# 4.net
KiCad netlist of a schematic drawn in Altium Designer
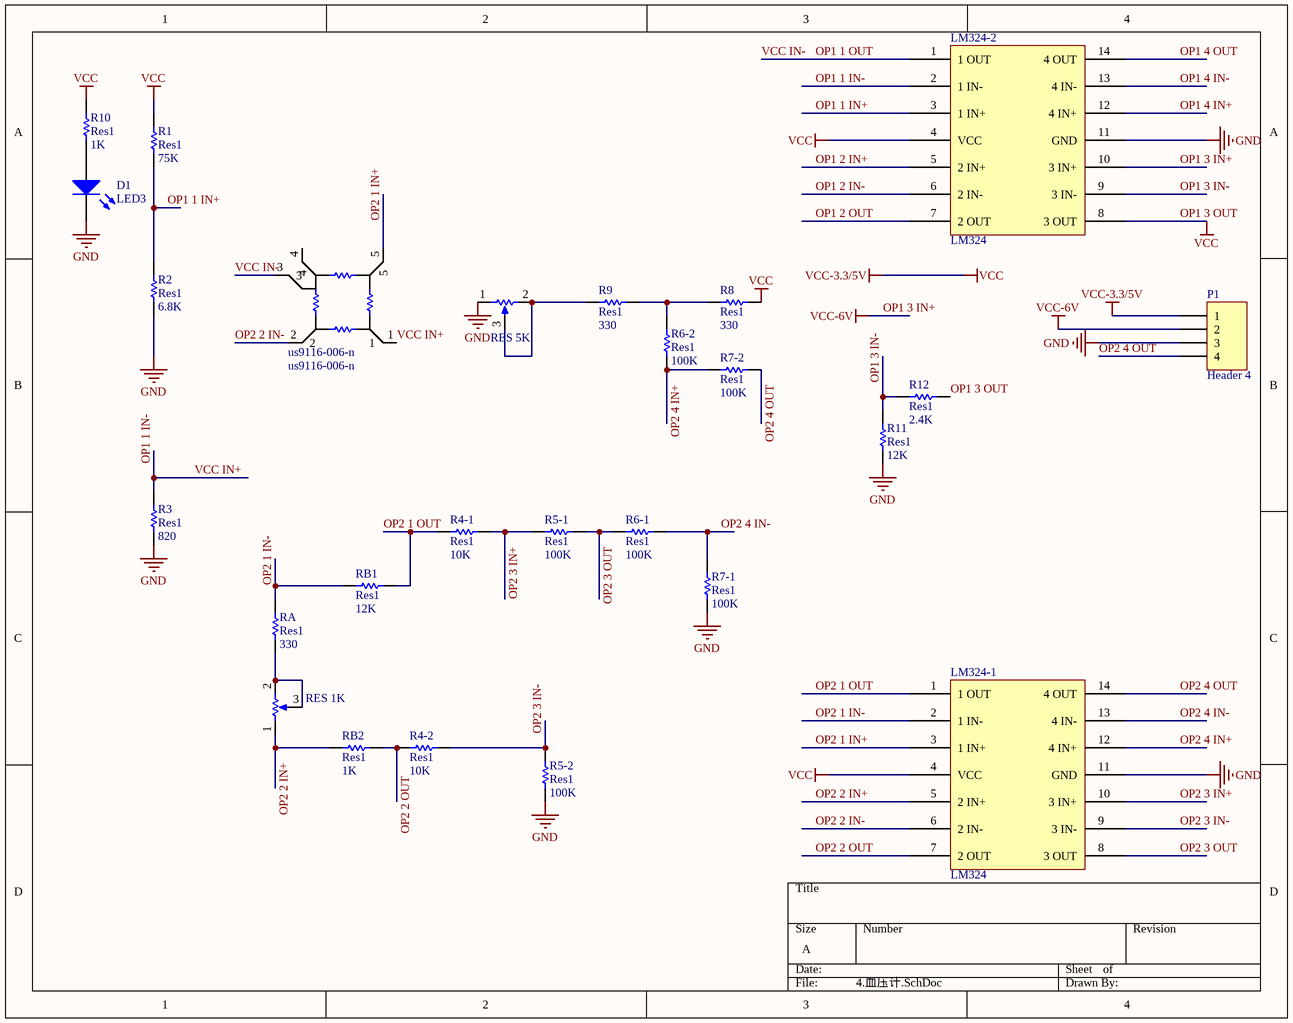
[diagram p0: 4.血压计.SchDoc]

(export (version "E")
  (design (tool "Eeschema 10.0.6"))
  (components
    (comp (ref "D1")
      (value "LED3")
      (footprint "LED/CAP/RES 0603")
      (description "Typical BLUE SiC LED")
      (fields (field (name "PUBLISHER") "Altium Limited"))
      (libsource (lib "Miscellaneous Devices") (part "LED3"))
    )
    (comp (ref "LM324-1")
      (value "LM324")
      (footprint "LM324")
      (libsource (lib "my Integrated lib ") (part "LM324"))
    )
    (comp (ref "LM324-2")
      (value "LM324")
      (footprint "LM324")
      (libsource (lib "my Integrated lib ") (part "LM324"))
    )
    (comp (ref "P1")
      (value "Header 4")
      (footprint "HDR1X4")
      (description "Header, 4-Pin")
      (fields (field (name "PUBLISHER") "Altium Limited"))
      (libsource (lib "Miscellaneous Connectors") (part "Header 4"))
    )
    (comp (ref "R1")
      (value "Res1")
      (footprint "LED/CAP/RES 0603")
      (description "Resistor")
      (fields (field (name "ALTIUM_VALUE") "75K") (field (name "PUBLISHER") "Altium Limited"))
      (libsource (lib "Miscellaneous Devices") (part "Res1"))
    )
    (comp (ref "R2")
      (value "Res1")
      (footprint "LED/CAP/RES 0603")
      (description "Resistor")
      (fields (field (name "ALTIUM_VALUE") "6.8K") (field (name "PUBLISHER") "Altium Limited"))
      (libsource (lib "Miscellaneous Devices") (part "Res1"))
    )
    (comp (ref "R3")
      (value "Res1")
      (footprint "LED/CAP/RES 0603")
      (description "Resistor")
      (fields (field (name "ALTIUM_VALUE") "820") (field (name "PUBLISHER") "Altium Limited"))
      (libsource (lib "Miscellaneous Devices") (part "Res1"))
    )
    (comp (ref "R4-1")
      (value "Res1")
      (footprint "LED/CAP/RES 0603")
      (description "Resistor")
      (fields (field (name "ALTIUM_VALUE") "10K") (field (name "PUBLISHER") "Altium Limited"))
      (libsource (lib "Miscellaneous Devices") (part "Res1"))
    )
    (comp (ref "R4-2")
      (value "Res1")
      (footprint "LED/CAP/RES 0603")
      (description "Resistor")
      (fields (field (name "ALTIUM_VALUE") "10K") (field (name "PUBLISHER") "Altium Limited"))
      (libsource (lib "Miscellaneous Devices") (part "Res1"))
    )
    (comp (ref "R5-1")
      (value "Res1")
      (footprint "LED/CAP/RES 0603")
      (description "Resistor")
      (fields (field (name "ALTIUM_VALUE") "100K") (field (name "PUBLISHER") "Altium Limited"))
      (libsource (lib "Miscellaneous Devices") (part "Res1"))
    )
    (comp (ref "R5-2")
      (value "Res1")
      (footprint "LED/CAP/RES 0603")
      (description "Resistor")
      (fields (field (name "ALTIUM_VALUE") "100K") (field (name "PUBLISHER") "Altium Limited"))
      (libsource (lib "Miscellaneous Devices") (part "Res1"))
    )
    (comp (ref "R6-1")
      (value "Res1")
      (footprint "LED/CAP/RES 0603")
      (description "Resistor")
      (fields (field (name "ALTIUM_VALUE") "100K") (field (name "PUBLISHER") "Altium Limited"))
      (libsource (lib "Miscellaneous Devices") (part "Res1"))
    )
    (comp (ref "R6-2")
      (value "Res1")
      (footprint "LED/CAP/RES 0603")
      (description "Resistor")
      (fields (field (name "ALTIUM_VALUE") "100K") (field (name "PUBLISHER") "Altium Limited"))
      (libsource (lib "Miscellaneous Devices") (part "Res1"))
    )
    (comp (ref "R7-1")
      (value "Res1")
      (footprint "LED/CAP/RES 0603")
      (description "Resistor")
      (fields (field (name "ALTIUM_VALUE") "100K") (field (name "PUBLISHER") "Altium Limited"))
      (libsource (lib "Miscellaneous Devices") (part "Res1"))
    )
    (comp (ref "R7-2")
      (value "Res1")
      (footprint "LED/CAP/RES 0603")
      (description "Resistor")
      (fields (field (name "ALTIUM_VALUE") "100K") (field (name "PUBLISHER") "Altium Limited"))
      (libsource (lib "Miscellaneous Devices") (part "Res1"))
    )
    (comp (ref "R8")
      (value "Res1")
      (footprint "LED/CAP/RES 0603")
      (description "Resistor")
      (fields (field (name "ALTIUM_VALUE") "330") (field (name "PUBLISHER") "Altium Limited"))
      (libsource (lib "Miscellaneous Devices") (part "Res1"))
    )
    (comp (ref "R9")
      (value "Res1")
      (footprint "LED/CAP/RES 0603")
      (description "Resistor")
      (fields (field (name "ALTIUM_VALUE") "330") (field (name "PUBLISHER") "Altium Limited"))
      (libsource (lib "Miscellaneous Devices") (part "Res1"))
    )
    (comp (ref "R10")
      (value "Res1")
      (footprint "LED/CAP/RES 0603")
      (description "Resistor")
      (fields (field (name "ALTIUM_VALUE") "1K") (field (name "PUBLISHER") "Altium Limited"))
      (libsource (lib "Miscellaneous Devices") (part "Res1"))
    )
    (comp (ref "R11")
      (value "Res1")
      (footprint "LED/CAP/RES 0603")
      (description "Resistor")
      (fields (field (name "ALTIUM_VALUE") "12K") (field (name "PUBLISHER") "Altium Limited"))
      (libsource (lib "Miscellaneous Devices") (part "Res1"))
    )
    (comp (ref "R12")
      (value "Res1")
      (footprint "LED/CAP/RES 0603")
      (description "Resistor")
      (fields (field (name "ALTIUM_VALUE") "2.4K") (field (name "PUBLISHER") "Altium Limited"))
      (libsource (lib "Miscellaneous Devices") (part "Res1"))
    )
    (comp (ref "RA")
      (value "Res1")
      (footprint "LED/CAP/RES 0603")
      (description "Resistor")
      (fields (field (name "ALTIUM_VALUE") "330") (field (name "PUBLISHER") "Altium Limited"))
      (libsource (lib "Miscellaneous Devices") (part "Res1"))
    )
    (comp (ref "RB1")
      (value "Res1")
      (footprint "LED/CAP/RES 0603")
      (description "Resistor")
      (fields (field (name "ALTIUM_VALUE") "12K") (field (name "PUBLISHER") "Altium Limited"))
      (libsource (lib "Miscellaneous Devices") (part "Res1"))
    )
    (comp (ref "RB2")
      (value "Res1")
      (footprint "LED/CAP/RES 0603")
      (description "Resistor")
      (fields (field (name "ALTIUM_VALUE") "1K") (field (name "PUBLISHER") "Altium Limited"))
      (libsource (lib "Miscellaneous Devices") (part "Res1"))
    )
    (comp (ref "RES 1K")
      (value "RES POT")
      (footprint "RES POT")
      (libsource (lib "my Integrated lib ") (part "RES POT"))
    )
    (comp (ref "RES 5K")
      (value "RES POT")
      (footprint "RES POT")
      (libsource (lib "my Integrated lib ") (part "RES POT"))
    )
    (comp (ref "us9116-006-n")
      (value "us9116-006-n")
      (footprint "us9116-006-n")
      (libsource (lib "my Integrated lib ") (part "us9116-006-n"))
    )
  )
  (nets
    (net (code "1") (name "/OP1 1 IN+") (class "Default")
      (node (ref "LM324-2") (pin "3") (pinfunction "1_IN+_3") (pintype "passive"))
      (node (ref "R1") (pin "1") (pinfunction "1_1") (pintype "passive"))
      (node (ref "R2") (pin "2") (pinfunction "2_2") (pintype "passive"))
    )
    (net (code "2") (name "/OP1 1 IN-") (class "Default")
      (node (ref "LM324-2") (pin "2") (pinfunction "1_IN-_2") (pintype "passive"))
      (node (ref "R3") (pin "1") (pinfunction "1_1") (pintype "passive"))
      (node (ref "us9116-006-n") (pin "1") (pinfunction "1_1") (pintype "passive"))
    )
    (net (code "3") (name "/OP1 1 OUT") (class "Default")
      (node (ref "LM324-2") (pin "1") (pinfunction "1_OUT_1") (pintype "passive"))
      (node (ref "us9116-006-n") (pin "3") (pinfunction "3_3") (pintype "passive"))
    )
    (net (code "4") (name "/OP1 2 IN+") (class "Default")
      (node (ref "LM324-2") (pin "5") (pinfunction "2_IN+_5") (pintype "passive"))
    )
    (net (code "5") (name "/OP1 2 IN-") (class "Default")
      (node (ref "LM324-2") (pin "6") (pinfunction "2_IN-_6") (pintype "passive"))
    )
    (net (code "6") (name "/OP1 2 OUT") (class "Default")
      (node (ref "LM324-2") (pin "7") (pinfunction "2_OUT_7") (pintype "passive"))
    )
    (net (code "7") (name "/OP1 3 IN-") (class "Default")
      (node (ref "LM324-2") (pin "9") (pinfunction "3_IN-_9") (pintype "passive"))
      (node (ref "R11") (pin "1") (pinfunction "1_1") (pintype "passive"))
      (node (ref "R12") (pin "2") (pinfunction "2_2") (pintype "passive"))
    )
    (net (code "8") (name "/OP1 4 IN+") (class "Default")
      (node (ref "LM324-2") (pin "12") (pinfunction "4_IN+_12") (pintype "passive"))
    )
    (net (code "9") (name "/OP1 4 IN-") (class "Default")
      (node (ref "LM324-2") (pin "13") (pinfunction "4_IN-_13") (pintype "passive"))
    )
    (net (code "10") (name "/OP1 4 OUT") (class "Default")
      (node (ref "LM324-2") (pin "14") (pinfunction "4_OUT_14") (pintype "passive"))
    )
    (net (code "11") (name "/OP2 1 IN+") (class "Default")
      (node (ref "LM324-1") (pin "3") (pinfunction "1_IN+_3") (pintype "passive"))
      (node (ref "us9116-006-n") (pin "5") (pinfunction "5_5") (pintype "passive"))
    )
    (net (code "12") (name "/OP2 1 IN-") (class "Default")
      (node (ref "LM324-1") (pin "2") (pinfunction "1_IN-_2") (pintype "passive"))
      (node (ref "RA") (pin "2") (pinfunction "2_2") (pintype "passive"))
      (node (ref "RB1") (pin "2") (pinfunction "2_2") (pintype "passive"))
    )
    (net (code "13") (name "/OP2 1 OUT") (class "Default")
      (node (ref "LM324-1") (pin "1") (pinfunction "1_OUT_1") (pintype "passive"))
      (node (ref "R4-1") (pin "2") (pinfunction "2_2") (pintype "passive"))
      (node (ref "RB1") (pin "1") (pinfunction "1_1") (pintype "passive"))
    )
    (net (code "14") (name "/OP2 2 IN+") (class "Default")
      (node (ref "LM324-1") (pin "5") (pinfunction "2_IN+_5") (pintype "passive"))
      (node (ref "RB2") (pin "2") (pinfunction "2_2") (pintype "passive"))
      (node (ref "RES 1K") (pin "1") (pinfunction "TOP_1") (pintype "passive"))
    )
    (net (code "15") (name "/OP2 2 IN-") (class "Default")
      (node (ref "LM324-1") (pin "6") (pinfunction "2_IN-_6") (pintype "passive"))
      (node (ref "us9116-006-n") (pin "2") (pinfunction "2_2") (pintype "passive"))
    )
    (net (code "16") (name "/OP2 2 OUT") (class "Default")
      (node (ref "LM324-1") (pin "7") (pinfunction "2_OUT_7") (pintype "passive"))
      (node (ref "R4-2") (pin "2") (pinfunction "2_2") (pintype "passive"))
      (node (ref "RB2") (pin "1") (pinfunction "1_1") (pintype "passive"))
    )
    (net (code "17") (name "/OP2 3 IN+") (class "Default")
      (node (ref "LM324-1") (pin "10") (pinfunction "3_IN+_10") (pintype "passive"))
      (node (ref "R4-1") (pin "1") (pinfunction "1_1") (pintype "passive"))
      (node (ref "R5-1") (pin "2") (pinfunction "2_2") (pintype "passive"))
    )
    (net (code "18") (name "/OP2 3 IN-") (class "Default")
      (node (ref "LM324-1") (pin "9") (pinfunction "3_IN-_9") (pintype "passive"))
      (node (ref "R4-2") (pin "1") (pinfunction "1_1") (pintype "passive"))
      (node (ref "R5-2") (pin "1") (pinfunction "1_1") (pintype "passive"))
    )
    (net (code "19") (name "/OP2 3 OUT") (class "Default")
      (node (ref "LM324-1") (pin "8") (pinfunction "3_OUT_8") (pintype "passive"))
      (node (ref "R5-1") (pin "1") (pinfunction "1_1") (pintype "passive"))
      (node (ref "R6-1") (pin "2") (pinfunction "2_2") (pintype "passive"))
    )
    (net (code "20") (name "/OP2 4 IN+") (class "Default")
      (node (ref "LM324-1") (pin "12") (pinfunction "4_IN+_12") (pintype "passive"))
      (node (ref "R6-2") (pin "2") (pinfunction "2_2") (pintype "passive"))
      (node (ref "R7-2") (pin "1") (pinfunction "1_1") (pintype "passive"))
    )
    (net (code "21") (name "/OP2 4 IN-") (class "Default")
      (node (ref "LM324-1") (pin "13") (pinfunction "4_IN-_13") (pintype "passive"))
      (node (ref "R6-1") (pin "1") (pinfunction "1_1") (pintype "passive"))
      (node (ref "R7-1") (pin "1") (pinfunction "1_1") (pintype "passive"))
    )
    (net (code "22") (name "/OP2 4 OUT") (class "Default")
      (node (ref "LM324-1") (pin "14") (pinfunction "4_OUT_14") (pintype "passive"))
      (node (ref "P1") (pin "4") (pinfunction "4_4") (pintype "passive"))
      (node (ref "R7-2") (pin "2") (pinfunction "2_2") (pintype "passive"))
    )
    (net (code "23") (name "GND") (class "Default")
      (node (ref "D1") (pin "2") (pinfunction "K_2") (pintype "passive"))
      (node (ref "LM324-1") (pin "11") (pinfunction "GND_11") (pintype "passive"))
      (node (ref "LM324-2") (pin "11") (pinfunction "GND_11") (pintype "passive"))
      (node (ref "P1") (pin "3") (pinfunction "3_3") (pintype "passive"))
      (node (ref "R11") (pin "2") (pinfunction "2_2") (pintype "passive"))
      (node (ref "R2") (pin "1") (pinfunction "1_1") (pintype "passive"))
      (node (ref "R3") (pin "2") (pinfunction "2_2") (pintype "passive"))
      (node (ref "R5-2") (pin "2") (pinfunction "2_2") (pintype "passive"))
      (node (ref "R7-1") (pin "2") (pinfunction "2_2") (pintype "passive"))
      (node (ref "RES 5K") (pin "1") (pinfunction "TOP_1") (pintype "passive"))
    )
    (net (code "24") (name "Net-(D1-A)") (class "Default")
      (node (ref "D1") (pin "1") (pinfunction "A_1") (pintype "passive"))
      (node (ref "R10") (pin "1") (pinfunction "1_1") (pintype "passive"))
    )
    (net (code "25") (name "Net-(R6-2-Pad1)") (class "Default")
      (node (ref "R6-2") (pin "1") (pinfunction "1_1") (pintype "passive"))
      (node (ref "R8") (pin "2") (pinfunction "2_2") (pintype "passive"))
      (node (ref "R9") (pin "1") (pinfunction "1_1") (pintype "passive"))
    )
    (net (code "26") (name "Net-(RES 1K-BOT)") (class "Default")
      (node (ref "RA") (pin "1") (pinfunction "1_1") (pintype "passive"))
      (node (ref "RES 1K") (pin "2") (pinfunction "BOT_2") (pintype "passive"))
      (node (ref "RES 1K") (pin "3") (pinfunction "TAP_3") (pintype "passive"))
    )
    (net (code "27") (name "Net-(RES 5K-BOT)") (class "Default")
      (node (ref "R9") (pin "2") (pinfunction "2_2") (pintype "passive"))
      (node (ref "RES 5K") (pin "2") (pinfunction "BOT_2") (pintype "passive"))
      (node (ref "RES 5K") (pin "3") (pinfunction "TAP_3") (pintype "passive"))
    )
    (net (code "28") (name "VCC") (class "Default")
      (node (ref "LM324-1") (pin "4") (pinfunction "VCC_4") (pintype "passive"))
      (node (ref "LM324-2") (pin "4") (pinfunction "VCC_4") (pintype "passive"))
      (node (ref "LM324-2") (pin "8") (pinfunction "3_OUT_8") (pintype "passive"))
      (node (ref "P1") (pin "1") (pinfunction "1_1") (pintype "passive"))
      (node (ref "R1") (pin "2") (pinfunction "2_2") (pintype "passive"))
      (node (ref "R10") (pin "2") (pinfunction "2_2") (pintype "passive"))
      (node (ref "R12") (pin "1") (pinfunction "1_1") (pintype "passive"))
      (node (ref "R8") (pin "1") (pinfunction "1_1") (pintype "passive"))
    )
    (net (code "29") (name "VCC-6V") (class "Default")
      (node (ref "LM324-2") (pin "10") (pinfunction "3_IN+_10") (pintype "passive"))
      (node (ref "P1") (pin "2") (pinfunction "2_2") (pintype "passive"))
    )
    (net (code "30") (name "unconnected-(us9116-006-n-Pad4)") (class "Default")
      (node (ref "us9116-006-n") (pin "4") (pinfunction "4_4") (pintype "passive"))
    )
  )
)
